# 1-Schematic_EMWAVER_V1_1.net
KiCad netlist of a schematic drawn in EasyEDA
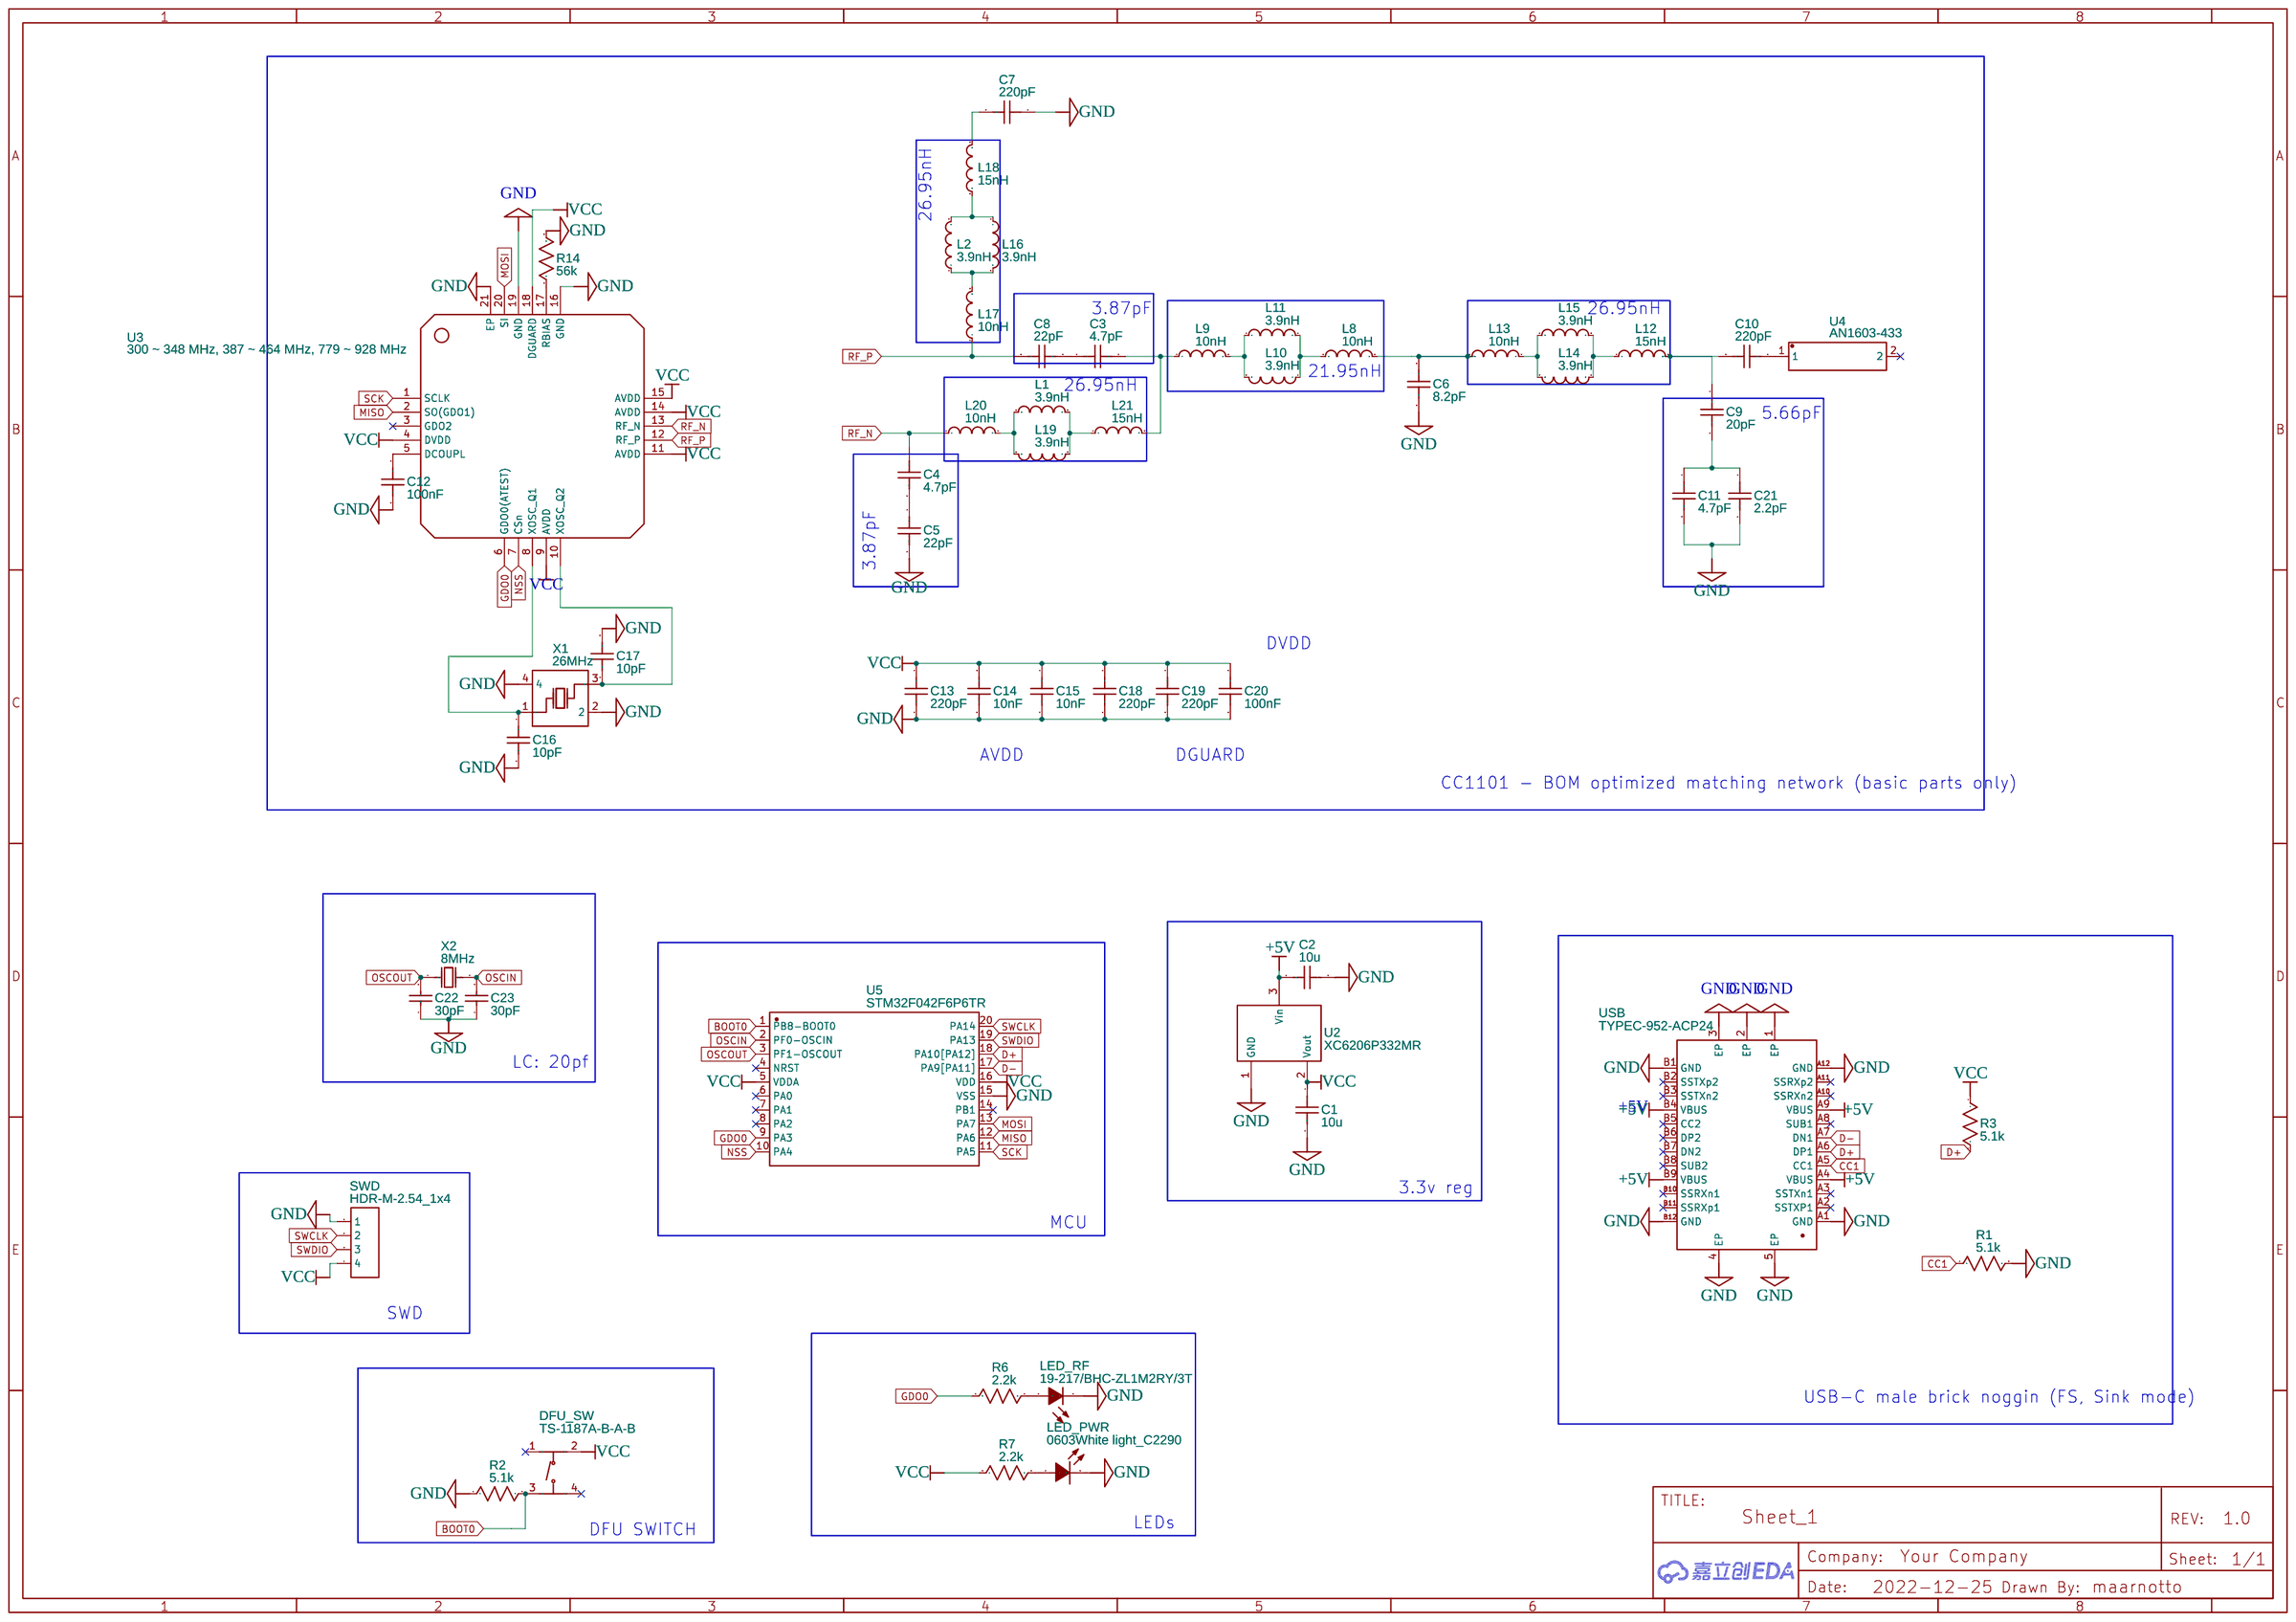
[diagram p0: schematic sheet]

(export (version "E")
  (design (tool "Eeschema 10.0.6"))
  (components
    (comp (ref "C1") (value "10u") (libsource (lib "") (part "C_0603_US")))
    (comp (ref "C2") (value "10u") (libsource (lib "") (part "C_0603_US_1")))
    (comp (ref "C3") (value "4.7pF") (libsource (lib "") (part "C_0402_US_1")))
    (comp (ref "C4") (value "4.7pF") (libsource (lib "") (part "C_0402_US")))
    (comp (ref "C5") (value "22pF") (libsource (lib "") (part "C_0402_US")))
    (comp (ref "C6") (value "8.2pF") (libsource (lib "") (part "C_0603_US")))
    (comp (ref "C7") (value "220pF") (libsource (lib "") (part "C_0402_US_1")))
    (comp (ref "C8") (value "22pF") (libsource (lib "") (part "C_0402_US_1")))
    (comp (ref "C9") (value "20pF") (libsource (lib "") (part "C_0402_US")))
    (comp (ref "C10") (value "220pF") (libsource (lib "") (part "C_0402_US_1")))
    (comp (ref "C11") (value "4.7pF") (libsource (lib "") (part "C_0402_US")))
    (comp (ref "C12") (value "100nF") (libsource (lib "") (part "C_0402_US")))
    (comp (ref "C13") (value "220pF") (libsource (lib "") (part "C_0402_US")))
    (comp (ref "C14") (value "10nF") (libsource (lib "") (part "C_0402_US")))
    (comp (ref "C15") (value "10nF") (libsource (lib "") (part "C_0402_US")))
    (comp (ref "C16") (value "10pF") (libsource (lib "") (part "C_0402_US")))
    (comp (ref "C17") (value "10pF") (libsource (lib "") (part "C_0402_US_2")))
    (comp (ref "C18") (value "220pF") (libsource (lib "") (part "C_0402_US")))
    (comp (ref "C19") (value "220pF") (libsource (lib "") (part "C_0402_US")))
    (comp (ref "C20") (value "100nF") (libsource (lib "") (part "C_0402_US")))
    (comp (ref "C21") (value "2.2pF") (libsource (lib "") (part "C_0402_US")))
    (comp (ref "C22")
      (value "30pF")
      (fields
        (field (name "BOM_Manufacturer Part") "0603CG300J500NT")
        (field (name "BOM_Supplier Part") "C1658")
      )
      (libsource (lib "") (part "0603CG300J500NT"))
    )
    (comp (ref "C23")
      (value "30pF")
      (fields
        (field (name "BOM_Manufacturer Part") "0603CG300J500NT")
        (field (name "BOM_Supplier Part") "C1658")
      )
      (libsource (lib "") (part "0603CG300J500NT"))
    )
    (comp (ref "DFU_SW")
      (value "TS-1187A-B-A-B")
      (fields (field (name "BOM_Supplier Part") "C318884"))
      (libsource (lib "") (part "TS-1187A-B-A-B"))
    )
    (comp (ref "L1")
      (value "3.9nH")
      (fields (field (name "BOM_Supplier Part") "C14033"))
      (libsource (lib "") (part "L0402_US_1"))
    )
    (comp (ref "L2")
      (value "3.9nH")
      (fields (field (name "BOM_Supplier Part") "C14033"))
      (libsource (lib "") (part "L0402_US"))
    )
    (comp (ref "L8")
      (value "10nH")
      (fields (field (name "BOM_Supplier Part") "C27147"))
      (libsource (lib "") (part "L0402_US_1"))
    )
    (comp (ref "L9")
      (value "10nH")
      (fields (field (name "BOM_Supplier Part") "C27147"))
      (libsource (lib "") (part "L0402_US_1"))
    )
    (comp (ref "L10")
      (value "3.9nH")
      (fields (field (name "BOM_Supplier Part") "C14033"))
      (libsource (lib "") (part "L0402_US_4"))
    )
    (comp (ref "L11")
      (value "3.9nH")
      (fields (field (name "BOM_Supplier Part") "C14033"))
      (libsource (lib "") (part "L0402_US_1"))
    )
    (comp (ref "L12")
      (value "15nH")
      (fields (field (name "BOM_Supplier Part") "C27143"))
      (libsource (lib "") (part "L0402_US_2"))
    )
    (comp (ref "L13")
      (value "10nH")
      (fields (field (name "BOM_Supplier Part") "C27147"))
      (libsource (lib "") (part "L0402_US_2"))
    )
    (comp (ref "L14")
      (value "3.9nH")
      (fields (field (name "BOM_Supplier Part") "C14033"))
      (libsource (lib "") (part "L0402_US_3"))
    )
    (comp (ref "L15")
      (value "3.9nH")
      (fields (field (name "BOM_Supplier Part") "C14033"))
      (libsource (lib "") (part "L0402_US_2"))
    )
    (comp (ref "L16")
      (value "3.9nH")
      (fields (field (name "BOM_Supplier Part") "C14033"))
      (libsource (lib "") (part "L0402_US_6"))
    )
    (comp (ref "L17")
      (value "10nH")
      (fields (field (name "BOM_Supplier Part") "C27147"))
      (libsource (lib "") (part "L0402_US"))
    )
    (comp (ref "L18")
      (value "15nH")
      (fields (field (name "BOM_Supplier Part") "C27143"))
      (libsource (lib "") (part "L0402_US_5"))
    )
    (comp (ref "L19")
      (value "3.9nH")
      (fields (field (name "BOM_Supplier Part") "C14033"))
      (libsource (lib "") (part "L0402_US_4"))
    )
    (comp (ref "L20")
      (value "10nH")
      (fields (field (name "BOM_Supplier Part") "C27147"))
      (libsource (lib "") (part "L0402_US_1"))
    )
    (comp (ref "L21")
      (value "15nH")
      (fields (field (name "BOM_Supplier Part") "C27143"))
      (libsource (lib "") (part "L0402_US_1"))
    )
    (comp (ref "LED_PWR")
      (value "0603White light_C2290")
      (fields (field (name "BOM_Manufacturer Part") "KT-0603白灯") (field (name "BOM_Supplier Part") "C2290"))
      (libsource (lib "") (part "0603White light_C2290"))
    )
    (comp (ref "LED_RF")
      (value "19-217/BHC-ZL1M2RY/3T")
      (fields (field (name "BOM_Supplier Part") "C72041"))
      (libsource (lib "") (part "19-217/BHC-ZL1M2RY/3T"))
    )
    (comp (ref "R1") (value "5.1k") (libsource (lib "") (part "R_0603_US")))
    (comp (ref "R2") (value "5.1k") (libsource (lib "") (part "R_0603_US")))
    (comp (ref "R3") (value "5.1k") (libsource (lib "") (part "R_0603_US_1")))
    (comp (ref "R6") (value "2.2k") (libsource (lib "") (part "R_0603_US")))
    (comp (ref "R7") (value "2.2k") (libsource (lib "") (part "R_0603_US")))
    (comp (ref "R14") (value "56k") (libsource (lib "") (part "R_0402_US")))
    (comp (ref "SWD")
      (value "HDR-M-2.54_1x4")
      (fields (field (name "BOM_Supplier Part") "C124378"))
      (libsource (lib "") (part "HDR-M-2.54_1x4"))
    )
    (comp (ref "U2")
      (value "XC6206P332MR")
      (fields (field (name "BOM_Supplier Part") "C5446"))
      (libsource (lib "") (part "XC6206P332MR"))
    )
    (comp (ref "U3")
      (value "300 ~ 348 MHz, 387 ~ 464 MHz, 779 ~ 928 MHz")
      (fields (field (name "BOM_Manufacturer Part") "CC1101RGPR") (field (name "BOM_Supplier Part") "C29953"))
      (libsource (lib "") (part "CC1101RGPR"))
    )
    (comp (ref "U4")
      (value "AN1603-433")
      (fields (field (name "BOM_Supplier Part") "C122806"))
      (libsource (lib "") (part "AN1603-433"))
    )
    (comp (ref "U5")
      (value "STM32F042F6P6TR")
      (fields (field (name "BOM_Supplier Part") "C2969989"))
      (libsource (lib "") (part "STM32F042F6P6TR"))
    )
    (comp (ref "USB")
      (value "TYPEC-952-ACP24")
      (fields (field (name "BOM_Supplier Part") "C2840398"))
      (libsource (lib "") (part "TYPEC-952-ACP24"))
    )
    (comp (ref "X1")
      (value "26MHz")
      (fields
        (field (name "BOM_Manufacturer Part") "3S26000333")
        (field (name "BOM_Supplier Part") "C431163")
      )
      (libsource (lib "") (part "3S26000333"))
    )
    (comp (ref "X2")
      (value "8MHz")
      (fields
        (field (name "BOM_Manufacturer Part") "X50328MSB2GI")
        (field (name "BOM_Supplier Part") "C115962")
      )
      (libsource (lib "") (part "X50328MSB2GI"))
    )
  )
  (nets
    (net (code "1") (name "+5V") (class "Default")
      (node (ref "C2") (pin "2") (pinfunction "2_2") (pintype "unspecified"))
      (node (ref "U2") (pin "3") (pinfunction "Vin_3") (pintype "unspecified"))
      (node (ref "USB") (pin "A4") (pinfunction "VBUS_A4") (pintype "unspecified"))
      (node (ref "USB") (pin "A9") (pinfunction "VBUS_A9") (pintype "unspecified"))
      (node (ref "USB") (pin "B4") (pinfunction "VBUS_B4") (pintype "unspecified"))
      (node (ref "USB") (pin "B9") (pinfunction "VBUS_B9") (pintype "unspecified"))
    )
    (net (code "2") (name "BOOT0") (class "Default")
      (node (ref "DFU_SW") (pin "3") (pinfunction "C_3") (pintype "unspecified"))
      (node (ref "R2") (pin "2") (pinfunction "2_2") (pintype "unspecified"))
      (node (ref "U5") (pin "1") (pinfunction "PB8-BOOT0_1") (pintype "unspecified"))
    )
    (net (code "3") (name "CC1") (class "Default")
      (node (ref "R1") (pin "1") (pinfunction "1_1") (pintype "unspecified"))
      (node (ref "USB") (pin "A5") (pinfunction "CC1_A5") (pintype "unspecified"))
    )
    (net (code "4") (name "D+") (class "Default")
      (node (ref "R3") (pin "2") (pinfunction "2_2") (pintype "unspecified"))
      (node (ref "U5") (pin "18") (pinfunction "PA10[PA12]_18") (pintype "unspecified"))
      (node (ref "USB") (pin "A6") (pinfunction "DP1_A6") (pintype "unspecified"))
    )
    (net (code "5") (name "D-") (class "Default")
      (node (ref "U5") (pin "17") (pinfunction "PA9[PA11]_17") (pintype "unspecified"))
      (node (ref "USB") (pin "A7") (pinfunction "DN1_A7") (pintype "unspecified"))
    )
    (net (code "6") (name "GDO0") (class "Default")
      (node (ref "R6") (pin "1") (pinfunction "1_1") (pintype "unspecified"))
      (node (ref "U3") (pin "6") (pinfunction "GDO0(ATEST)_6") (pintype "unspecified"))
      (node (ref "U5") (pin "9") (pinfunction "PA3_9") (pintype "unspecified"))
    )
    (net (code "7") (name "GND") (class "Default")
      (node (ref "C1") (pin "2") (pinfunction "2_2") (pintype "unspecified"))
      (node (ref "C11") (pin "2") (pinfunction "2_2") (pintype "unspecified"))
      (node (ref "C12") (pin "2") (pinfunction "2_2") (pintype "unspecified"))
      (node (ref "C13") (pin "2") (pinfunction "2_2") (pintype "unspecified"))
      (node (ref "C14") (pin "2") (pinfunction "2_2") (pintype "unspecified"))
      (node (ref "C15") (pin "2") (pinfunction "2_2") (pintype "unspecified"))
      (node (ref "C16") (pin "2") (pinfunction "2_2") (pintype "unspecified"))
      (node (ref "C17") (pin "2") (pinfunction "2_2") (pintype "unspecified"))
      (node (ref "C18") (pin "2") (pinfunction "2_2") (pintype "unspecified"))
      (node (ref "C19") (pin "2") (pinfunction "2_2") (pintype "unspecified"))
      (node (ref "C2") (pin "1") (pinfunction "1_1") (pintype "unspecified"))
      (node (ref "C20") (pin "2") (pinfunction "2_2") (pintype "unspecified"))
      (node (ref "C21") (pin "2") (pinfunction "2_2") (pintype "unspecified"))
      (node (ref "C22") (pin "1") (pinfunction "1_1") (pintype "input"))
      (node (ref "C23") (pin "1") (pinfunction "1_1") (pintype "input"))
      (node (ref "C5") (pin "2") (pinfunction "2_2") (pintype "unspecified"))
      (node (ref "C6") (pin "2") (pinfunction "2_2") (pintype "unspecified"))
      (node (ref "C7") (pin "1") (pinfunction "1_1") (pintype "unspecified"))
      (node (ref "LED_PWR") (pin "2") (pinfunction "K_2") (pintype "unspecified"))
      (node (ref "LED_RF") (pin "1") (pinfunction "C_1") (pintype "input"))
      (node (ref "R1") (pin "2") (pinfunction "2_2") (pintype "unspecified"))
      (node (ref "R14") (pin "2") (pinfunction "2_2") (pintype "unspecified"))
      (node (ref "R2") (pin "1") (pinfunction "1_1") (pintype "unspecified"))
      (node (ref "SWD") (pin "1") (pinfunction "1_1") (pintype "unspecified"))
      (node (ref "U2") (pin "1") (pinfunction "GND_1") (pintype "unspecified"))
      (node (ref "U3") (pin "16") (pinfunction "GND_16") (pintype "unspecified"))
      (node (ref "U3") (pin "19") (pinfunction "GND_19") (pintype "unspecified"))
      (node (ref "U3") (pin "21") (pinfunction "EP_21") (pintype "unspecified"))
      (node (ref "U5") (pin "15") (pinfunction "VSS_15") (pintype "unspecified"))
      (node (ref "USB") (pin "1") (pinfunction "EP_1") (pintype "unspecified"))
      (node (ref "USB") (pin "2") (pinfunction "EP_2") (pintype "unspecified"))
      (node (ref "USB") (pin "3") (pinfunction "EP_3") (pintype "unspecified"))
      (node (ref "USB") (pin "4") (pinfunction "EP_4") (pintype "unspecified"))
      (node (ref "USB") (pin "5") (pinfunction "EP_5") (pintype "unspecified"))
      (node (ref "USB") (pin "A1") (pinfunction "GND_A1") (pintype "unspecified"))
      (node (ref "USB") (pin "A12") (pinfunction "GND_A12") (pintype "unspecified"))
      (node (ref "USB") (pin "B1") (pinfunction "GND_B1") (pintype "unspecified"))
      (node (ref "USB") (pin "B12") (pinfunction "GND_B12") (pintype "unspecified"))
      (node (ref "X1") (pin "2") (pinfunction "2_2") (pintype "unspecified"))
      (node (ref "X1") (pin "4") (pinfunction "4_4") (pintype "unspecified"))
    )
    (net (code "8") (name "MISO") (class "Default")
      (node (ref "U3") (pin "2") (pinfunction "SO(GDO1)_2") (pintype "unspecified"))
      (node (ref "U5") (pin "12") (pinfunction "PA6_12") (pintype "unspecified"))
    )
    (net (code "9") (name "MOSI") (class "Default")
      (node (ref "U3") (pin "20") (pinfunction "SI_20") (pintype "unspecified"))
      (node (ref "U5") (pin "13") (pinfunction "PA7_13") (pintype "unspecified"))
    )
    (net (code "10") (name "NSS") (class "Default")
      (node (ref "U3") (pin "7") (pinfunction "CSn_7") (pintype "unspecified"))
      (node (ref "U5") (pin "10") (pinfunction "PA4_10") (pintype "unspecified"))
    )
    (net (code "11") (name "Net-(C3-Pad1)") (class "Default")
      (node (ref "C3") (pin "1") (pinfunction "1_1") (pintype "unspecified"))
      (node (ref "L21") (pin "2") (pinfunction "2_2") (pintype "unspecified"))
      (node (ref "L9") (pin "1") (pinfunction "1_1") (pintype "unspecified"))
    )
    (net (code "12") (name "Net-(C3-Pad2)") (class "Default")
      (node (ref "C3") (pin "2") (pinfunction "2_2") (pintype "unspecified"))
      (node (ref "C8") (pin "1") (pinfunction "1_1") (pintype "unspecified"))
    )
    (net (code "13") (name "Net-(C4-Pad2)") (class "Default")
      (node (ref "C4") (pin "2") (pinfunction "2_2") (pintype "unspecified"))
      (node (ref "C5") (pin "1") (pinfunction "1_1") (pintype "unspecified"))
    )
    (net (code "14") (name "Net-(C6-Pad1)") (class "Default")
      (node (ref "C6") (pin "1") (pinfunction "1_1") (pintype "unspecified"))
      (node (ref "L13") (pin "1") (pinfunction "1_1") (pintype "unspecified"))
      (node (ref "L8") (pin "2") (pinfunction "2_2") (pintype "unspecified"))
    )
    (net (code "15") (name "Net-(C7-Pad2)") (class "Default")
      (node (ref "C7") (pin "2") (pinfunction "2_2") (pintype "unspecified"))
      (node (ref "L18") (pin "2") (pinfunction "2_2") (pintype "unspecified"))
    )
    (net (code "16") (name "Net-(C10-Pad1)") (class "Default")
      (node (ref "C10") (pin "1") (pinfunction "1_1") (pintype "unspecified"))
      (node (ref "U4") (pin "1") (pinfunction "1_1") (pintype "unspecified"))
    )
    (net (code "17") (name "Net-(C10-Pad2)") (class "Default")
      (node (ref "C10") (pin "2") (pinfunction "2_2") (pintype "unspecified"))
      (node (ref "C9") (pin "1") (pinfunction "1_1") (pintype "unspecified"))
      (node (ref "L12") (pin "2") (pinfunction "2_2") (pintype "unspecified"))
    )
    (net (code "18") (name "Net-(C11-Pad1)") (class "Default")
      (node (ref "C11") (pin "1") (pinfunction "1_1") (pintype "unspecified"))
      (node (ref "C21") (pin "1") (pinfunction "1_1") (pintype "unspecified"))
      (node (ref "C9") (pin "2") (pinfunction "2_2") (pintype "unspecified"))
    )
    (net (code "19") (name "Net-(L1-Pad1)") (class "Default")
      (node (ref "L1") (pin "1") (pinfunction "1_1") (pintype "unspecified"))
      (node (ref "L19") (pin "2") (pinfunction "2_2") (pintype "unspecified"))
      (node (ref "L20") (pin "2") (pinfunction "2_2") (pintype "unspecified"))
    )
    (net (code "20") (name "Net-(L1-Pad2)") (class "Default")
      (node (ref "L1") (pin "2") (pinfunction "2_2") (pintype "unspecified"))
      (node (ref "L19") (pin "1") (pinfunction "1_1") (pintype "unspecified"))
      (node (ref "L21") (pin "1") (pinfunction "1_1") (pintype "unspecified"))
    )
    (net (code "21") (name "Net-(L10-Pad1)") (class "Default")
      (node (ref "L10") (pin "1") (pinfunction "1_1") (pintype "unspecified"))
      (node (ref "L11") (pin "2") (pinfunction "2_2") (pintype "unspecified"))
      (node (ref "L8") (pin "1") (pinfunction "1_1") (pintype "unspecified"))
    )
    (net (code "22") (name "Net-(L10-Pad2)") (class "Default")
      (node (ref "L10") (pin "2") (pinfunction "2_2") (pintype "unspecified"))
      (node (ref "L11") (pin "1") (pinfunction "1_1") (pintype "unspecified"))
      (node (ref "L9") (pin "2") (pinfunction "2_2") (pintype "unspecified"))
    )
    (net (code "23") (name "Net-(L12-Pad1)") (class "Default")
      (node (ref "L12") (pin "1") (pinfunction "1_1") (pintype "unspecified"))
      (node (ref "L14") (pin "1") (pinfunction "1_1") (pintype "unspecified"))
      (node (ref "L15") (pin "2") (pinfunction "2_2") (pintype "unspecified"))
    )
    (net (code "24") (name "Net-(L13-Pad2)") (class "Default")
      (node (ref "L13") (pin "2") (pinfunction "2_2") (pintype "unspecified"))
      (node (ref "L14") (pin "2") (pinfunction "2_2") (pintype "unspecified"))
      (node (ref "L15") (pin "1") (pinfunction "1_1") (pintype "unspecified"))
    )
    (net (code "25") (name "Net-(L16-Pad1)") (class "Default")
      (node (ref "L16") (pin "1") (pinfunction "1_1") (pintype "unspecified"))
      (node (ref "L18") (pin "1") (pinfunction "1_1") (pintype "unspecified"))
      (node (ref "L2") (pin "2") (pinfunction "2_2") (pintype "unspecified"))
    )
    (net (code "26") (name "Net-(L16-Pad2)") (class "Default")
      (node (ref "L16") (pin "2") (pinfunction "2_2") (pintype "unspecified"))
      (node (ref "L17") (pin "2") (pinfunction "2_2") (pintype "unspecified"))
      (node (ref "L2") (pin "1") (pinfunction "1_1") (pintype "unspecified"))
    )
    (net (code "27") (name "Net-(LED_PWR-A)") (class "Default")
      (node (ref "LED_PWR") (pin "1") (pinfunction "A_1") (pintype "unspecified"))
      (node (ref "R7") (pin "2") (pinfunction "2_2") (pintype "unspecified"))
    )
    (net (code "28") (name "Net-(LED_RF-A)") (class "Default")
      (node (ref "LED_RF") (pin "2") (pinfunction "A_2") (pintype "input"))
      (node (ref "R6") (pin "2") (pinfunction "2_2") (pintype "unspecified"))
    )
    (net (code "29") (name "Net-(U3-DCOUPL)") (class "Default")
      (node (ref "C12") (pin "1") (pinfunction "1_1") (pintype "unspecified"))
      (node (ref "U3") (pin "5") (pinfunction "DCOUPL_5") (pintype "unspecified"))
    )
    (net (code "30") (name "Net-(U3-RBIAS)") (class "Default")
      (node (ref "R14") (pin "1") (pinfunction "1_1") (pintype "unspecified"))
      (node (ref "U3") (pin "17") (pinfunction "RBIAS_17") (pintype "unspecified"))
    )
    (net (code "31") (name "Net-(U3-XOSC_Q1)") (class "Default")
      (node (ref "C16") (pin "1") (pinfunction "1_1") (pintype "unspecified"))
      (node (ref "U3") (pin "8") (pinfunction "XOSC_Q1_8") (pintype "unspecified"))
      (node (ref "X1") (pin "1") (pinfunction "OSC1_1") (pintype "unspecified"))
    )
    (net (code "32") (name "Net-(U3-XOSC_Q2)") (class "Default")
      (node (ref "C17") (pin "1") (pinfunction "1_1") (pintype "unspecified"))
      (node (ref "U3") (pin "10") (pinfunction "XOSC_Q2_10") (pintype "unspecified"))
      (node (ref "X1") (pin "3") (pinfunction "OSC2_3") (pintype "unspecified"))
    )
    (net (code "33") (name "OSCIN") (class "Default")
      (node (ref "C23") (pin "2") (pinfunction "2_2") (pintype "input"))
      (node (ref "U5") (pin "2") (pinfunction "PF0-OSCIN_2") (pintype "unspecified"))
      (node (ref "X2") (pin "2") (pinfunction "OSC2_2") (pintype "input"))
    )
    (net (code "34") (name "OSCOUT") (class "Default")
      (node (ref "C22") (pin "2") (pinfunction "2_2") (pintype "input"))
      (node (ref "U5") (pin "3") (pinfunction "PF1-OSCOUT_3") (pintype "unspecified"))
      (node (ref "X2") (pin "1") (pinfunction "OSC1_1") (pintype "input"))
    )
    (net (code "35") (name "RF_N") (class "Default")
      (node (ref "C4") (pin "1") (pinfunction "1_1") (pintype "unspecified"))
      (node (ref "L20") (pin "1") (pinfunction "1_1") (pintype "unspecified"))
      (node (ref "U3") (pin "13") (pinfunction "RF_N_13") (pintype "unspecified"))
    )
    (net (code "36") (name "RF_P") (class "Default")
      (node (ref "C8") (pin "2") (pinfunction "2_2") (pintype "unspecified"))
      (node (ref "L17") (pin "1") (pinfunction "1_1") (pintype "unspecified"))
      (node (ref "U3") (pin "12") (pinfunction "RF_P_12") (pintype "unspecified"))
    )
    (net (code "37") (name "SCK") (class "Default")
      (node (ref "U3") (pin "1") (pinfunction "SCLK_1") (pintype "unspecified"))
      (node (ref "U5") (pin "11") (pinfunction "PA5_11") (pintype "unspecified"))
    )
    (net (code "38") (name "SWCLK") (class "Default")
      (node (ref "SWD") (pin "2") (pinfunction "2_2") (pintype "unspecified"))
      (node (ref "U5") (pin "20") (pinfunction "PA14_20") (pintype "unspecified"))
    )
    (net (code "39") (name "SWDIO") (class "Default")
      (node (ref "SWD") (pin "3") (pinfunction "3_3") (pintype "unspecified"))
      (node (ref "U5") (pin "19") (pinfunction "PA13_19") (pintype "unspecified"))
    )
    (net (code "40") (name "VCC") (class "Default")
      (node (ref "C1") (pin "1") (pinfunction "1_1") (pintype "unspecified"))
      (node (ref "C13") (pin "1") (pinfunction "1_1") (pintype "unspecified"))
      (node (ref "C14") (pin "1") (pinfunction "1_1") (pintype "unspecified"))
      (node (ref "C15") (pin "1") (pinfunction "1_1") (pintype "unspecified"))
      (node (ref "C18") (pin "1") (pinfunction "1_1") (pintype "unspecified"))
      (node (ref "C19") (pin "1") (pinfunction "1_1") (pintype "unspecified"))
      (node (ref "C20") (pin "1") (pinfunction "1_1") (pintype "unspecified"))
      (node (ref "DFU_SW") (pin "2") (pinfunction "B_2") (pintype "unspecified"))
      (node (ref "R3") (pin "1") (pinfunction "1_1") (pintype "unspecified"))
      (node (ref "R7") (pin "1") (pinfunction "1_1") (pintype "unspecified"))
      (node (ref "SWD") (pin "4") (pinfunction "4_4") (pintype "unspecified"))
      (node (ref "U2") (pin "2") (pinfunction "Vout_2") (pintype "unspecified"))
      (node (ref "U3") (pin "11") (pinfunction "AVDD_11") (pintype "unspecified"))
      (node (ref "U3") (pin "14") (pinfunction "AVDD_14") (pintype "unspecified"))
      (node (ref "U3") (pin "15") (pinfunction "AVDD_15") (pintype "unspecified"))
      (node (ref "U3") (pin "18") (pinfunction "DGUARD_18") (pintype "unspecified"))
      (node (ref "U3") (pin "4") (pinfunction "DVDD_4") (pintype "unspecified"))
      (node (ref "U3") (pin "9") (pinfunction "AVDD_9") (pintype "unspecified"))
      (node (ref "U5") (pin "16") (pinfunction "VDD_16") (pintype "unspecified"))
      (node (ref "U5") (pin "5") (pinfunction "VDDA_5") (pintype "unspecified"))
    )
    (net (code "41") (name "unconnected-(DFU_SW-A-Pad1)") (class "Default")
      (node (ref "DFU_SW") (pin "1") (pinfunction "A_1") (pintype "unspecified+no_connect"))
    )
    (net (code "42") (name "unconnected-(DFU_SW-D-Pad4)") (class "Default")
      (node (ref "DFU_SW") (pin "4") (pinfunction "D_4") (pintype "unspecified+no_connect"))
    )
    (net (code "43") (name "unconnected-(U3-GDO2-Pad3)") (class "Default")
      (node (ref "U3") (pin "3") (pinfunction "GDO2_3") (pintype "unspecified+no_connect"))
    )
    (net (code "44") (name "unconnected-(U4-Pad2)") (class "Default")
      (node (ref "U4") (pin "2") (pinfunction "2_2") (pintype "unspecified+no_connect"))
    )
    (net (code "45") (name "unconnected-(U5-NRST-Pad4)") (class "Default")
      (node (ref "U5") (pin "4") (pinfunction "NRST_4") (pintype "unspecified+no_connect"))
    )
    (net (code "46") (name "unconnected-(U5-PA0-Pad6)") (class "Default")
      (node (ref "U5") (pin "6") (pinfunction "PA0_6") (pintype "unspecified+no_connect"))
    )
    (net (code "47") (name "unconnected-(U5-PA1-Pad7)") (class "Default")
      (node (ref "U5") (pin "7") (pinfunction "PA1_7") (pintype "unspecified+no_connect"))
    )
    (net (code "48") (name "unconnected-(U5-PA2-Pad8)") (class "Default")
      (node (ref "U5") (pin "8") (pinfunction "PA2_8") (pintype "unspecified+no_connect"))
    )
    (net (code "49") (name "unconnected-(U5-PB1-Pad14)") (class "Default")
      (node (ref "U5") (pin "14") (pinfunction "PB1_14") (pintype "unspecified+no_connect"))
    )
    (net (code "50") (name "unconnected-(USB-CC2-PadB5)") (class "Default")
      (node (ref "USB") (pin "B5") (pinfunction "CC2_B5") (pintype "unspecified+no_connect"))
    )
    (net (code "51") (name "unconnected-(USB-DN2-PadB7)") (class "Default")
      (node (ref "USB") (pin "B7") (pinfunction "DN2_B7") (pintype "unspecified+no_connect"))
    )
    (net (code "52") (name "unconnected-(USB-DP2-PadB6)") (class "Default")
      (node (ref "USB") (pin "B6") (pinfunction "DP2_B6") (pintype "unspecified+no_connect"))
    )
    (net (code "53") (name "unconnected-(USB-SSRXn1-PadB10)") (class "Default")
      (node (ref "USB") (pin "B10") (pinfunction "SSRXn1_B10") (pintype "unspecified+no_connect"))
    )
    (net (code "54") (name "unconnected-(USB-SSRXn2-PadA10)") (class "Default")
      (node (ref "USB") (pin "A10") (pinfunction "SSRXn2_A10") (pintype "unspecified+no_connect"))
    )
    (net (code "55") (name "unconnected-(USB-SSRXp1-PadB11)") (class "Default")
      (node (ref "USB") (pin "B11") (pinfunction "SSRXp1_B11") (pintype "unspecified+no_connect"))
    )
    (net (code "56") (name "unconnected-(USB-SSRXp2-PadA11)") (class "Default")
      (node (ref "USB") (pin "A11") (pinfunction "SSRXp2_A11") (pintype "unspecified+no_connect"))
    )
    (net (code "57") (name "unconnected-(USB-SSTXP1-PadA2)") (class "Default")
      (node (ref "USB") (pin "A2") (pinfunction "SSTXP1_A2") (pintype "unspecified+no_connect"))
    )
    (net (code "58") (name "unconnected-(USB-SSTXn1-PadA3)") (class "Default")
      (node (ref "USB") (pin "A3") (pinfunction "SSTXn1_A3") (pintype "unspecified+no_connect"))
    )
    (net (code "59") (name "unconnected-(USB-SSTXn2-PadB3)") (class "Default")
      (node (ref "USB") (pin "B3") (pinfunction "SSTXn2_B3") (pintype "unspecified+no_connect"))
    )
    (net (code "60") (name "unconnected-(USB-SSTXp2-PadB2)") (class "Default")
      (node (ref "USB") (pin "B2") (pinfunction "SSTXp2_B2") (pintype "unspecified+no_connect"))
    )
    (net (code "61") (name "unconnected-(USB-SUB1-PadA8)") (class "Default")
      (node (ref "USB") (pin "A8") (pinfunction "SUB1_A8") (pintype "unspecified+no_connect"))
    )
    (net (code "62") (name "unconnected-(USB-SUB2-PadB8)") (class "Default")
      (node (ref "USB") (pin "B8") (pinfunction "SUB2_B8") (pintype "unspecified+no_connect"))
    )
  )
)
